# ShiftReg_Accel.net
KiCad netlist of a schematic drawn in EAGLE
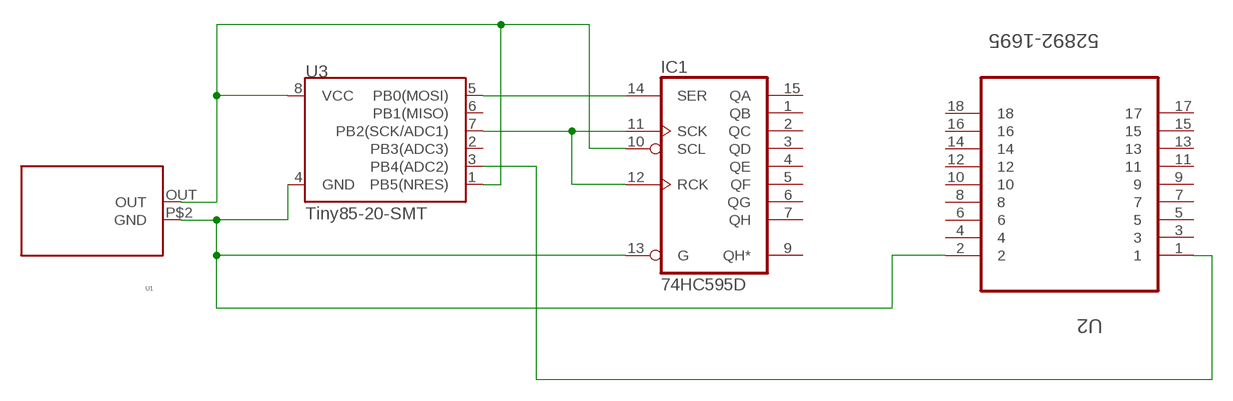
[diagram p0: schematic, sheet 1]

(export (version "E")
  (design (tool "Eeschema 10.0.6"))
  (components
    (comp (ref "IC1")
      (value "74HC595D")
      (footprint "eagle-import:SO16")
      (libsource (lib "eagle-import") (part "74595DHC"))
    )
    (comp (ref "U1")
      (value "P9027LP-R")
      (footprint "eagle-import:P9027LP-R")
      (libsource (lib "eagle-import") (part "P9027LP-R"))
    )
    (comp (ref "U2")
      (value "52892-1695")
      (footprint "eagle-import:MOLEX_52892-1695")
      (libsource (lib "eagle-import") (part "52892-1695"))
    )
    (comp (ref "U3")
      (value "Tiny85-20-SMT")
      (footprint "eagle-import:SO08-EIAJ")
      (libsource (lib "eagle-import") (part "ATTINY45TINY85-20-SMT"))
    )
  )
  (nets
    (net (code "1") (name "Net-(IC1A-G)") (class "Default")
      (node (ref "IC1") (pin "13") (pinfunction "G_13") (pintype "input"))
      (node (ref "U1") (pin "P$2") (pinfunction "GND_P$2") (pintype "power_in"))
      (node (ref "U2") (pin "2") (pinfunction "2_2") (pintype "passive"))
      (node (ref "U3") (pin "4") (pinfunction "GND_4") (pintype "bidirectional"))
    )
    (net (code "2") (name "Net-(IC1A-RCK)") (class "Default")
      (node (ref "IC1") (pin "11") (pinfunction "SCK_11") (pintype "input"))
      (node (ref "IC1") (pin "12") (pinfunction "RCK_12") (pintype "input"))
      (node (ref "U3") (pin "7") (pinfunction "PB2(SCK/ADC1)_7") (pintype "bidirectional"))
    )
    (net (code "3") (name "Net-(IC1A-SCL)") (class "Default")
      (node (ref "IC1") (pin "10") (pinfunction "SCL_10") (pintype "input"))
      (node (ref "U1") (pin "OUT") (pinfunction "OUT_OUT") (pintype "power_in"))
      (node (ref "U3") (pin "1") (pinfunction "PB5(NRES)_1") (pintype "bidirectional"))
      (node (ref "U3") (pin "8") (pinfunction "VCC_8") (pintype "bidirectional"))
    )
    (net (code "4") (name "Net-(IC1A-SER)") (class "Default")
      (node (ref "IC1") (pin "14") (pinfunction "SER_14") (pintype "input"))
      (node (ref "U3") (pin "5") (pinfunction "PB0(MOSI)_5") (pintype "bidirectional"))
    )
    (net (code "5") (name "Net-(U3-PB4(ADC2))") (class "Default")
      (node (ref "U2") (pin "1") (pinfunction "1_1") (pintype "passive"))
      (node (ref "U3") (pin "3") (pinfunction "PB4(ADC2)_3") (pintype "bidirectional"))
    )
    (net (code "6") (name "unconnected-(IC1A-QA-Pad15)") (class "Default")
      (node (ref "IC1") (pin "15") (pinfunction "QA_15") (pintype "tri_state"))
    )
    (net (code "7") (name "unconnected-(IC1A-QB-Pad1)") (class "Default")
      (node (ref "IC1") (pin "1") (pinfunction "QB_1") (pintype "tri_state"))
    )
    (net (code "8") (name "unconnected-(IC1A-QC-Pad2)") (class "Default")
      (node (ref "IC1") (pin "2") (pinfunction "QC_2") (pintype "tri_state"))
    )
    (net (code "9") (name "unconnected-(IC1A-QD-Pad3)") (class "Default")
      (node (ref "IC1") (pin "3") (pinfunction "QD_3") (pintype "tri_state"))
    )
    (net (code "10") (name "unconnected-(IC1A-QE-Pad4)") (class "Default")
      (node (ref "IC1") (pin "4") (pinfunction "QE_4") (pintype "tri_state"))
    )
    (net (code "11") (name "unconnected-(IC1A-QF-Pad5)") (class "Default")
      (node (ref "IC1") (pin "5") (pinfunction "QF_5") (pintype "tri_state"))
    )
    (net (code "12") (name "unconnected-(IC1A-QG-Pad6)") (class "Default")
      (node (ref "IC1") (pin "6") (pinfunction "QG_6") (pintype "tri_state"))
    )
    (net (code "13") (name "unconnected-(IC1A-QH*-Pad9)") (class "Default")
      (node (ref "IC1") (pin "9") (pinfunction "QH*_9") (pintype "tri_state"))
    )
    (net (code "14") (name "unconnected-(IC1A-QH-Pad7)") (class "Default")
      (node (ref "IC1") (pin "7") (pinfunction "QH_7") (pintype "tri_state"))
    )
    (net (code "15") (name "unconnected-(U2-Pad3)") (class "Default")
      (node (ref "U2") (pin "3") (pinfunction "3_3") (pintype "passive"))
    )
    (net (code "16") (name "unconnected-(U2-Pad4)") (class "Default")
      (node (ref "U2") (pin "4") (pinfunction "4_4") (pintype "passive"))
    )
    (net (code "17") (name "unconnected-(U2-Pad5)") (class "Default")
      (node (ref "U2") (pin "5") (pinfunction "5_5") (pintype "passive"))
    )
    (net (code "18") (name "unconnected-(U2-Pad6)") (class "Default")
      (node (ref "U2") (pin "6") (pinfunction "6_6") (pintype "passive"))
    )
    (net (code "19") (name "unconnected-(U2-Pad7)") (class "Default")
      (node (ref "U2") (pin "7") (pinfunction "7_7") (pintype "passive"))
    )
    (net (code "20") (name "unconnected-(U2-Pad8)") (class "Default")
      (node (ref "U2") (pin "8") (pinfunction "8_8") (pintype "passive"))
    )
    (net (code "21") (name "unconnected-(U2-Pad9)") (class "Default")
      (node (ref "U2") (pin "9") (pinfunction "9_9") (pintype "passive"))
    )
    (net (code "22") (name "unconnected-(U2-Pad10)") (class "Default")
      (node (ref "U2") (pin "10") (pinfunction "10_10") (pintype "passive"))
    )
    (net (code "23") (name "unconnected-(U2-Pad11)") (class "Default")
      (node (ref "U2") (pin "11") (pinfunction "11_11") (pintype "passive"))
    )
    (net (code "24") (name "unconnected-(U2-Pad12)") (class "Default")
      (node (ref "U2") (pin "12") (pinfunction "12_12") (pintype "passive"))
    )
    (net (code "25") (name "unconnected-(U2-Pad13)") (class "Default")
      (node (ref "U2") (pin "13") (pinfunction "13_13") (pintype "passive"))
    )
    (net (code "26") (name "unconnected-(U2-Pad14)") (class "Default")
      (node (ref "U2") (pin "14") (pinfunction "14_14") (pintype "passive"))
    )
    (net (code "27") (name "unconnected-(U2-Pad15)") (class "Default")
      (node (ref "U2") (pin "15") (pinfunction "15_15") (pintype "passive"))
    )
    (net (code "28") (name "unconnected-(U2-Pad16)") (class "Default")
      (node (ref "U2") (pin "16") (pinfunction "16_16") (pintype "passive"))
    )
    (net (code "29") (name "unconnected-(U2-Pad17)") (class "Default")
      (node (ref "U2") (pin "17") (pinfunction "17_17") (pintype "passive"))
    )
    (net (code "30") (name "unconnected-(U2-Pad18)") (class "Default")
      (node (ref "U2") (pin "18") (pinfunction "18_18") (pintype "passive"))
    )
    (net (code "31") (name "unconnected-(U3-PB1(MISO)-Pad6)") (class "Default")
      (node (ref "U3") (pin "6") (pinfunction "PB1(MISO)_6") (pintype "bidirectional"))
    )
    (net (code "32") (name "unconnected-(U3-PB3(ADC3)-Pad2)") (class "Default")
      (node (ref "U3") (pin "2") (pinfunction "PB3(ADC3)_2") (pintype "bidirectional"))
    )
  )
)
